# untitled.net
KiCad netlist of a schematic drawn in EAGLE
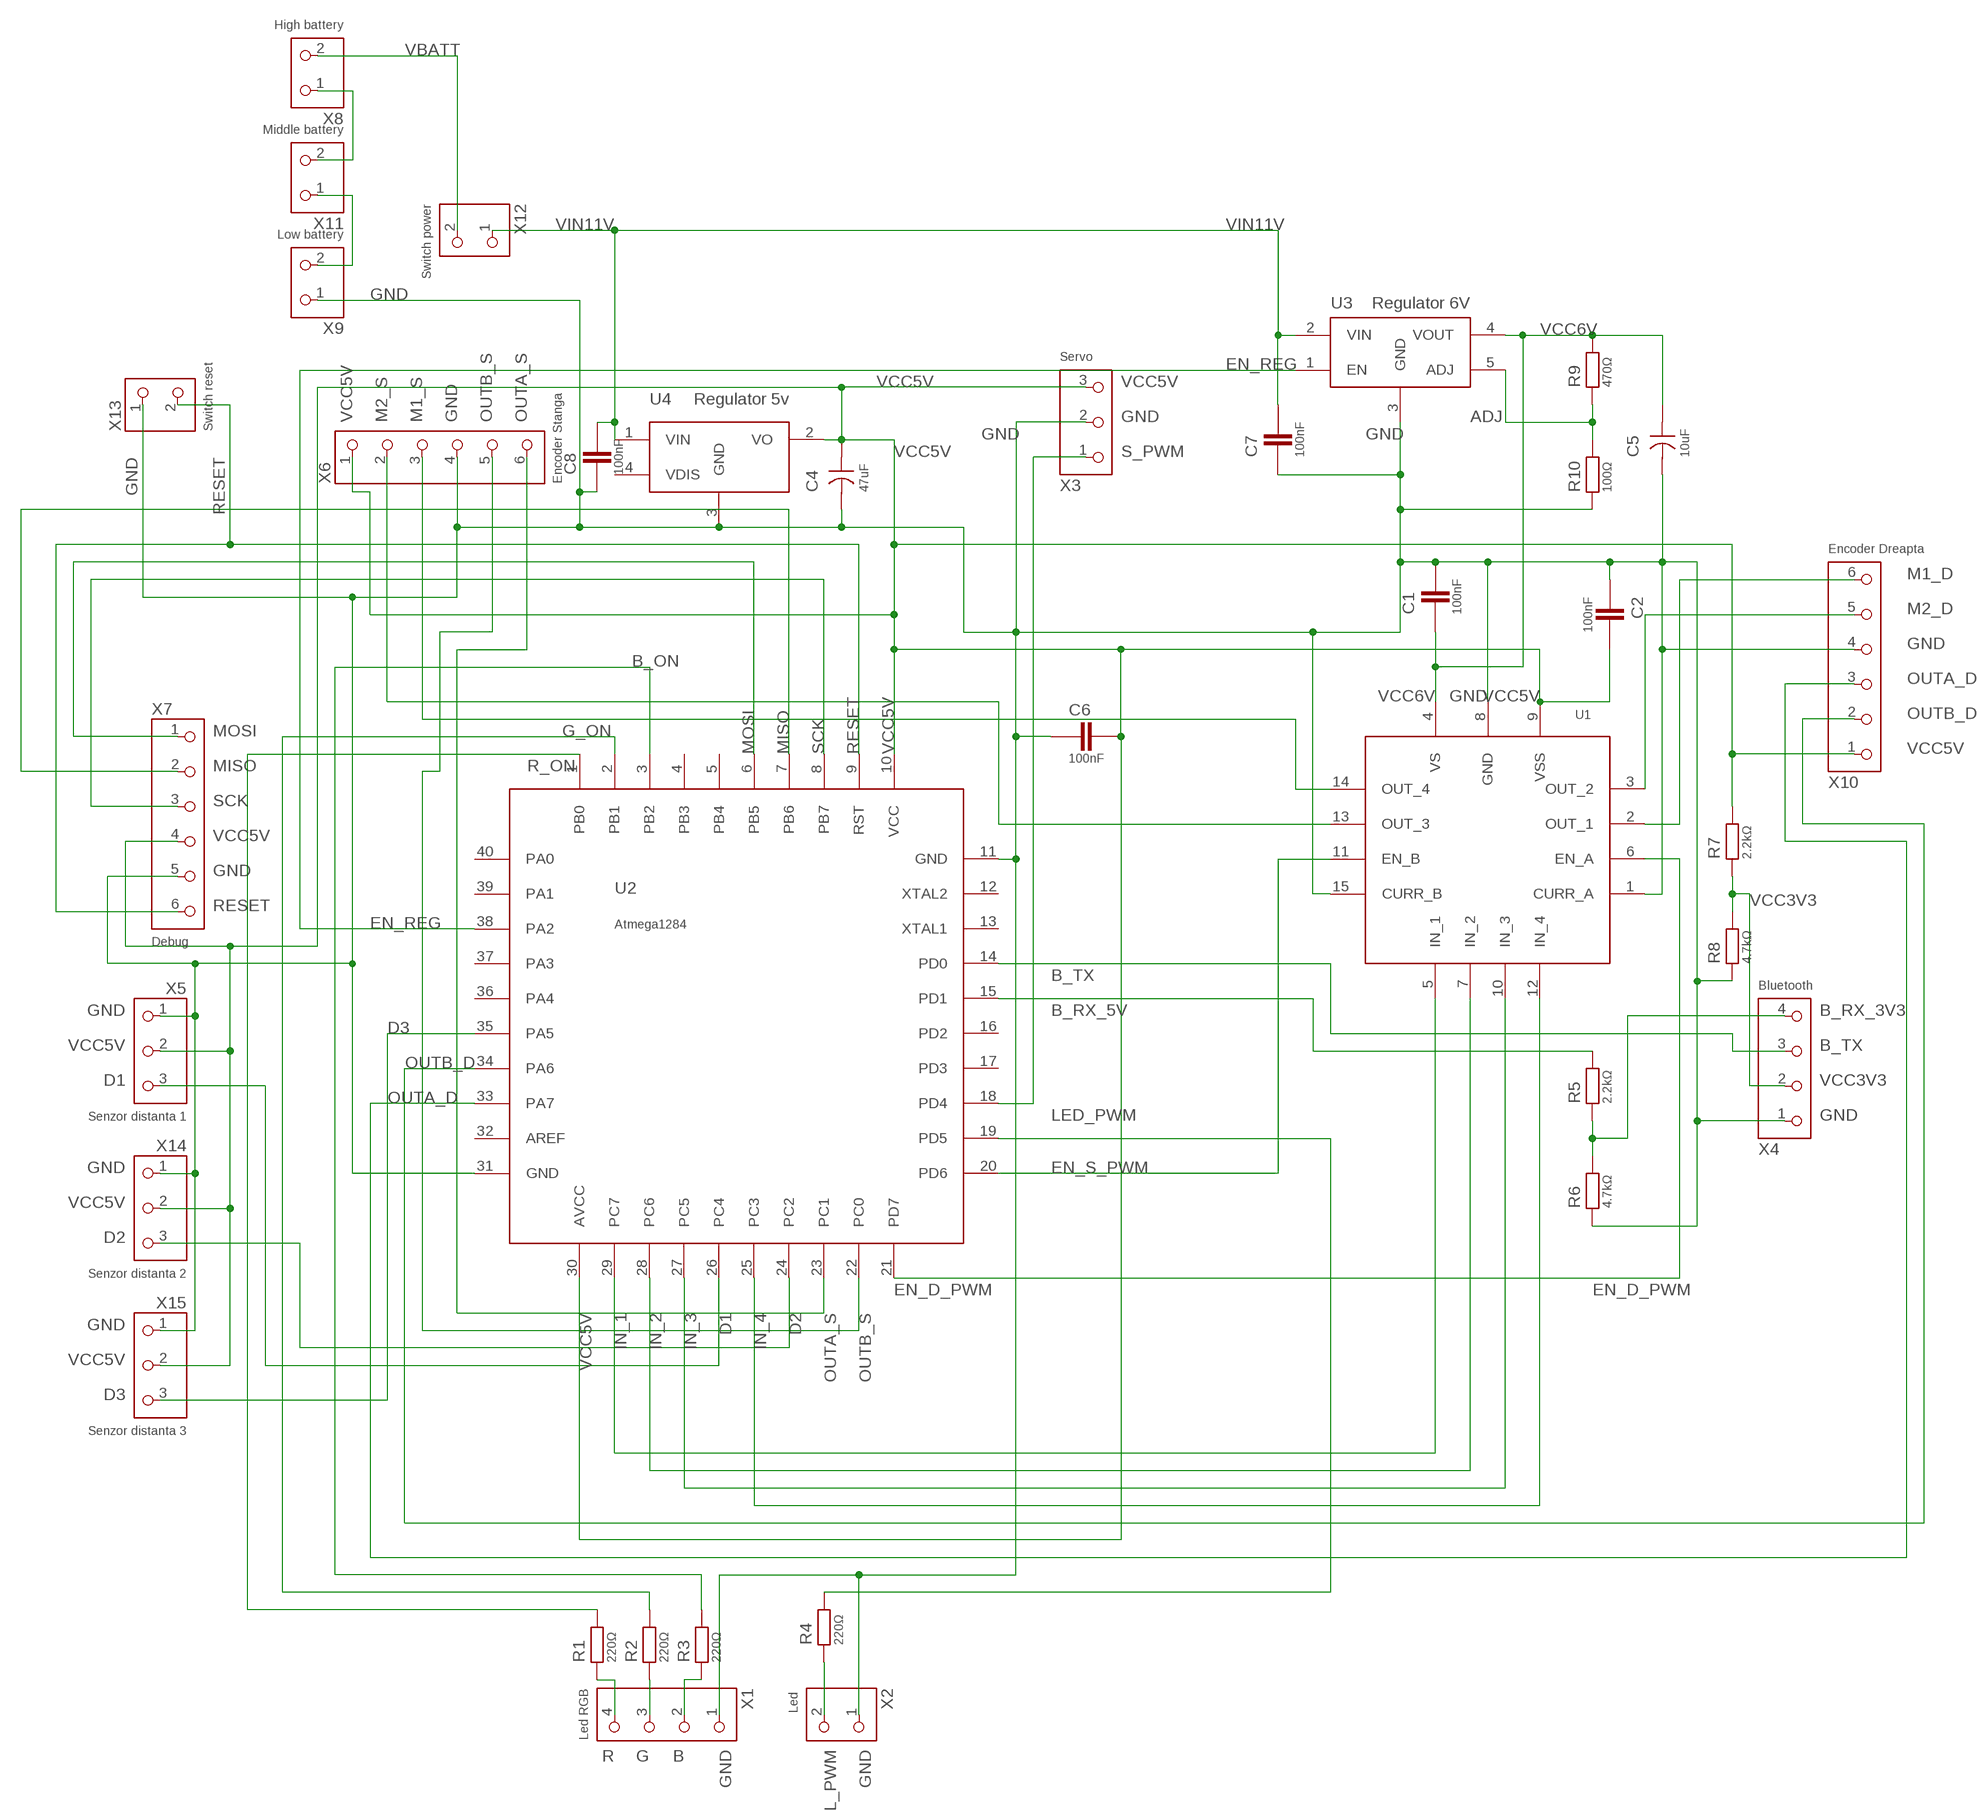
[diagram p0: schematic, sheet 1]

(export (version "E")
  (design (tool "Eeschema 10.0.6"))
  (components
    (comp (ref "C1")
      (value "100nF")
      (footprint "eagle-import:THT_2.54")
      (libsource (lib "eagle-import") (part "CAPACITORTHT_2.54"))
    )
    (comp (ref "C2")
      (value "100nF")
      (footprint "eagle-import:THT_2.54")
      (libsource (lib "eagle-import") (part "CAPACITORTHT_2.54"))
    )
    (comp (ref "C4")
      (value "47uF")
      (footprint "eagle-import:ELECTROLYTIC_5MM_PEFRBOARD")
      (libsource (lib "eagle-import") (part "ELECTROLYTIC_CAPACITOR5MM_PERFBOARD"))
    )
    (comp (ref "C5")
      (value "10uF")
      (footprint "eagle-import:ELECTROLYTIC_5MM_PEFRBOARD")
      (libsource (lib "eagle-import") (part "ELECTROLYTIC_CAPACITOR5MM_PERFBOARD"))
    )
    (comp (ref "C6")
      (value "100nF")
      (footprint "eagle-import:THT_2.54")
      (libsource (lib "eagle-import") (part "CAPACITORTHT_2.54"))
    )
    (comp (ref "C7")
      (value "100nF")
      (footprint "eagle-import:THT_2.54")
      (libsource (lib "eagle-import") (part "CAPACITORTHT_2.54"))
    )
    (comp (ref "C8")
      (value "100nF")
      (footprint "eagle-import:THT_2.54")
      (libsource (lib "eagle-import") (part "CAPACITORTHT_2.54"))
    )
    (comp (ref "R1")
      (value "220Ω")
      (footprint "eagle-import:THT_5.08")
      (libsource (lib "eagle-import") (part "RESISTORTHT_5.08"))
    )
    (comp (ref "R2")
      (value "220Ω")
      (footprint "eagle-import:THT_5.08")
      (libsource (lib "eagle-import") (part "RESISTORTHT_5.08"))
    )
    (comp (ref "R3")
      (value "220Ω")
      (footprint "eagle-import:THT_5.08")
      (libsource (lib "eagle-import") (part "RESISTORTHT_5.08"))
    )
    (comp (ref "R4")
      (value "220Ω")
      (footprint "eagle-import:THT_5.08")
      (libsource (lib "eagle-import") (part "RESISTORTHT_5.08"))
    )
    (comp (ref "R5")
      (value "2.2kΩ")
      (footprint "eagle-import:THT_2.54")
      (libsource (lib "eagle-import") (part "RESISTORTHT_2.54"))
    )
    (comp (ref "R6")
      (value "4.7kΩ")
      (footprint "eagle-import:THT_5.08")
      (libsource (lib "eagle-import") (part "RESISTORTHT_5.08"))
    )
    (comp (ref "R7")
      (value "2.2kΩ")
      (footprint "eagle-import:THT_5.08")
      (libsource (lib "eagle-import") (part "RESISTORTHT_5.08"))
    )
    (comp (ref "R8")
      (value "4.7kΩ")
      (footprint "eagle-import:THT_5.08")
      (libsource (lib "eagle-import") (part "RESISTORTHT_5.08"))
    )
    (comp (ref "R9")
      (value "470Ω")
      (footprint "eagle-import:THT_2.54")
      (libsource (lib "eagle-import") (part "RESISTORTHT_2.54"))
    )
    (comp (ref "R10")
      (value "100Ω")
      (footprint "eagle-import:THT_5.08")
      (libsource (lib "eagle-import") (part "RESISTORTHT_5.08"))
    )
    (comp (ref "U1")
      (value "L298NMULTIWATT15V_PERFBOARD")
      (footprint "eagle-import:MULTIWATT15V_PERFBOARD")
      (libsource (lib "eagle-import") (part "L298NMULTIWATT15V_PERFBOARD"))
    )
    (comp (ref "U2")
      (value "Atmega1284")
      (footprint "eagle-import:DIP-40")
      (libsource (lib "eagle-import") (part "ATMEGAPDIP"))
    )
    (comp (ref "U3")
      (value "Regulator 6V")
      (footprint "eagle-import:TO-220-5_PERFBOARD")
      (libsource (lib "eagle-import") (part "MIC29XXPERFBOARD"))
    )
    (comp (ref "U4")
      (value "Regulator 5v")
      (footprint "eagle-import:TO-220-4")
      (libsource (lib "eagle-import") (part "KA78R05C"))
    )
    (comp (ref "X1")
      (value "Led RGB")
      (footprint "eagle-import:MALE_PIN_1X4")
      (libsource (lib "eagle-import") (part "CONNECTOR_4PIN"))
    )
    (comp (ref "X2")
      (value "Led")
      (footprint "eagle-import:MALE_PIN_1X2")
      (libsource (lib "eagle-import") (part "CONNECTOR_2PINMALE_PIN"))
    )
    (comp (ref "X3")
      (value "Servo")
      (footprint "eagle-import:MALE_PIN_1X3")
      (libsource (lib "eagle-import") (part "CONNECTOR_3PIN"))
    )
    (comp (ref "X4")
      (value "Bluetooth")
      (footprint "eagle-import:MALE_PIN_1X4")
      (libsource (lib "eagle-import") (part "CONNECTOR_4PIN"))
    )
    (comp (ref "X5")
      (value "Senzor distanta 1")
      (footprint "eagle-import:MALE_PIN_1X3")
      (libsource (lib "eagle-import") (part "CONNECTOR_3PIN"))
    )
    (comp (ref "X6")
      (value "Encoder Stanga")
      (footprint "eagle-import:MALE_PIN_2X3")
      (libsource (lib "eagle-import") (part "CONNECTOR_6PIN2X3"))
    )
    (comp (ref "X7")
      (value "Debug")
      (footprint "eagle-import:MALE_PIN_2X3")
      (libsource (lib "eagle-import") (part "CONNECTOR_6PIN2X3"))
    )
    (comp (ref "X8")
      (value "High battery")
      (footprint "eagle-import:FEMALE_SCREW_1X2")
      (libsource (lib "eagle-import") (part "CONNECTOR_2PINFEMALE_SCREW"))
    )
    (comp (ref "X9")
      (value "Low battery")
      (footprint "eagle-import:FEMALE_SCREW_1X2")
      (libsource (lib "eagle-import") (part "CONNECTOR_2PINFEMALE_SCREW"))
    )
    (comp (ref "X10")
      (value "Encoder Dreapta")
      (footprint "eagle-import:MALE_PIN_2X3")
      (libsource (lib "eagle-import") (part "CONNECTOR_6PIN2X3"))
    )
    (comp (ref "X11")
      (value "Middle battery")
      (footprint "eagle-import:FEMALE_SCREW_1X2")
      (libsource (lib "eagle-import") (part "CONNECTOR_2PINFEMALE_SCREW"))
    )
    (comp (ref "X12")
      (value "Switch power")
      (footprint "eagle-import:MALE_PIN_1X2")
      (libsource (lib "eagle-import") (part "CONNECTOR_2PINMALE_PIN"))
    )
    (comp (ref "X13")
      (value "Switch reset")
      (footprint "eagle-import:MALE_PIN_1X2")
      (libsource (lib "eagle-import") (part "CONNECTOR_2PINMALE_PIN"))
    )
    (comp (ref "X14")
      (value "Senzor distanta 2")
      (footprint "eagle-import:MALE_PIN_1X3")
      (libsource (lib "eagle-import") (part "CONNECTOR_3PIN"))
    )
    (comp (ref "X15")
      (value "Senzor distanta 3")
      (footprint "eagle-import:MALE_PIN_1X3")
      (libsource (lib "eagle-import") (part "CONNECTOR_3PIN"))
    )
  )
  (nets
    (net (code "1") (name "/ADJ") (class "Default")
      (node (ref "R10") (pin "2") (pinfunction "P$2_2") (pintype "passive"))
      (node (ref "R9") (pin "1") (pinfunction "P$1_1") (pintype "passive"))
      (node (ref "U3") (pin "5") (pinfunction "ADJ_5") (pintype "input"))
    )
    (net (code "2") (name "/B") (class "Default")
      (node (ref "R3") (pin "1") (pinfunction "P$1_1") (pintype "passive"))
      (node (ref "X1") (pin "2") (pinfunction "2_2") (pintype "passive"))
    )
    (net (code "3") (name "/B_ON") (class "Default")
      (node (ref "R3") (pin "2") (pinfunction "P$2_2") (pintype "passive"))
      (node (ref "U2") (pin "3") (pinfunction "PB2_3") (pintype "bidirectional"))
    )
    (net (code "4") (name "/B_RX_3V3") (class "Default")
      (node (ref "R5") (pin "1") (pinfunction "P$1_1") (pintype "passive"))
      (node (ref "R6") (pin "2") (pinfunction "P$2_2") (pintype "passive"))
      (node (ref "X4") (pin "4") (pinfunction "4_4") (pintype "passive"))
    )
    (net (code "5") (name "/B_RX_5V") (class "Default")
      (node (ref "R5") (pin "2") (pinfunction "P$2_2") (pintype "passive"))
      (node (ref "U2") (pin "15") (pinfunction "PD1_15") (pintype "bidirectional"))
    )
    (net (code "6") (name "/B_TX") (class "Default")
      (node (ref "U2") (pin "14") (pinfunction "PD0_14") (pintype "bidirectional"))
      (node (ref "X4") (pin "3") (pinfunction "3_3") (pintype "passive"))
    )
    (net (code "7") (name "/D1") (class "Default")
      (node (ref "U2") (pin "26") (pinfunction "PC4_26") (pintype "bidirectional"))
      (node (ref "X5") (pin "3") (pinfunction "3_3") (pintype "passive"))
    )
    (net (code "8") (name "/D2") (class "Default")
      (node (ref "U2") (pin "24") (pinfunction "PC2_24") (pintype "bidirectional"))
      (node (ref "X14") (pin "3") (pinfunction "3_3") (pintype "passive"))
    )
    (net (code "9") (name "/D3") (class "Default")
      (node (ref "U2") (pin "35") (pinfunction "PA5_35") (pintype "bidirectional"))
      (node (ref "X15") (pin "3") (pinfunction "3_3") (pintype "passive"))
    )
    (net (code "10") (name "/EN_D_PWM") (class "Default")
      (node (ref "U1") (pin "6") (pinfunction "EN_A_6") (pintype "input"))
      (node (ref "U2") (pin "21") (pinfunction "PD7_21") (pintype "bidirectional"))
    )
    (net (code "11") (name "/EN_REG") (class "Default")
      (node (ref "U2") (pin "38") (pinfunction "PA2_38") (pintype "bidirectional"))
      (node (ref "U3") (pin "1") (pinfunction "EN_1") (pintype "input"))
    )
    (net (code "12") (name "/EN_S_PWM") (class "Default")
      (node (ref "U1") (pin "11") (pinfunction "EN_B_11") (pintype "input"))
      (node (ref "U2") (pin "20") (pinfunction "PD6_20") (pintype "bidirectional"))
    )
    (net (code "13") (name "/G") (class "Default")
      (node (ref "R2") (pin "1") (pinfunction "P$1_1") (pintype "passive"))
      (node (ref "X1") (pin "3") (pinfunction "3_3") (pintype "passive"))
    )
    (net (code "14") (name "/GND") (class "Default")
      (node (ref "C1") (pin "2") (pinfunction "P$2_2") (pintype "passive"))
      (node (ref "C2") (pin "1") (pinfunction "P$1_1") (pintype "passive"))
      (node (ref "C4") (pin "-") (pinfunction "-_-") (pintype "passive"))
      (node (ref "C5") (pin "-") (pinfunction "-_-") (pintype "passive"))
      (node (ref "C6") (pin "1") (pinfunction "P$1_1") (pintype "passive"))
      (node (ref "C7") (pin "1") (pinfunction "P$1_1") (pintype "passive"))
      (node (ref "C8") (pin "1") (pinfunction "P$1_1") (pintype "passive"))
      (node (ref "R10") (pin "1") (pinfunction "P$1_1") (pintype "passive"))
      (node (ref "R6") (pin "1") (pinfunction "P$1_1") (pintype "passive"))
      (node (ref "R8") (pin "1") (pinfunction "P$1_1") (pintype "passive"))
      (node (ref "U1") (pin "1") (pinfunction "CURR_A_1") (pintype "output"))
      (node (ref "U1") (pin "15") (pinfunction "CURR_B_15") (pintype "output"))
      (node (ref "U1") (pin "8") (pinfunction "GND_8") (pintype "power_in"))
      (node (ref "U2") (pin "11") (pinfunction "GND_11") (pintype "power_in"))
      (node (ref "U2") (pin "31") (pinfunction "GND_31") (pintype "power_in"))
      (node (ref "U3") (pin "3") (pinfunction "GND_3") (pintype "power_in"))
      (node (ref "U4") (pin "3") (pinfunction "GND_3") (pintype "power_in"))
      (node (ref "X1") (pin "1") (pinfunction "1_1") (pintype "passive"))
      (node (ref "X10") (pin "4") (pinfunction "4_4") (pintype "passive"))
      (node (ref "X13") (pin "1") (pinfunction "1_1") (pintype "passive"))
      (node (ref "X14") (pin "1") (pinfunction "1_1") (pintype "passive"))
      (node (ref "X15") (pin "1") (pinfunction "1_1") (pintype "passive"))
      (node (ref "X2") (pin "1") (pinfunction "1_1") (pintype "passive"))
      (node (ref "X3") (pin "2") (pinfunction "2_2") (pintype "passive"))
      (node (ref "X4") (pin "1") (pinfunction "1_1") (pintype "passive"))
      (node (ref "X5") (pin "1") (pinfunction "1_1") (pintype "passive"))
      (node (ref "X6") (pin "4") (pinfunction "4_4") (pintype "passive"))
      (node (ref "X7") (pin "5") (pinfunction "5_5") (pintype "passive"))
      (node (ref "X9") (pin "1") (pinfunction "1_1") (pintype "passive"))
    )
    (net (code "15") (name "/G_ON") (class "Default")
      (node (ref "R2") (pin "2") (pinfunction "P$2_2") (pintype "passive"))
      (node (ref "U2") (pin "2") (pinfunction "PB1_2") (pintype "bidirectional"))
    )
    (net (code "16") (name "/IN_1") (class "Default")
      (node (ref "U1") (pin "5") (pinfunction "IN_1_5") (pintype "input"))
      (node (ref "U2") (pin "29") (pinfunction "PC7_29") (pintype "bidirectional"))
    )
    (net (code "17") (name "/IN_2") (class "Default")
      (node (ref "U1") (pin "7") (pinfunction "IN_2_7") (pintype "input"))
      (node (ref "U2") (pin "28") (pinfunction "PC6_28") (pintype "bidirectional"))
    )
    (net (code "18") (name "/IN_3") (class "Default")
      (node (ref "U1") (pin "10") (pinfunction "IN_3_10") (pintype "input"))
      (node (ref "U2") (pin "27") (pinfunction "PC5_27") (pintype "bidirectional"))
    )
    (net (code "19") (name "/IN_4") (class "Default")
      (node (ref "U1") (pin "12") (pinfunction "IN_4_12") (pintype "input"))
      (node (ref "U2") (pin "25") (pinfunction "PC3_25") (pintype "bidirectional"))
    )
    (net (code "20") (name "/LED_PWM") (class "Default")
      (node (ref "R4") (pin "2") (pinfunction "P$2_2") (pintype "passive"))
      (node (ref "U2") (pin "19") (pinfunction "PD5_19") (pintype "bidirectional"))
    )
    (net (code "21") (name "/L_PWM") (class "Default")
      (node (ref "R4") (pin "1") (pinfunction "P$1_1") (pintype "passive"))
      (node (ref "X2") (pin "2") (pinfunction "2_2") (pintype "passive"))
    )
    (net (code "22") (name "/M1_D") (class "Default")
      (node (ref "U1") (pin "2") (pinfunction "OUT_1_2") (pintype "output"))
      (node (ref "X10") (pin "6") (pinfunction "6_6") (pintype "passive"))
    )
    (net (code "23") (name "/M1_S") (class "Default")
      (node (ref "U1") (pin "14") (pinfunction "OUT_4_14") (pintype "output"))
      (node (ref "X6") (pin "3") (pinfunction "3_3") (pintype "passive"))
    )
    (net (code "24") (name "/M2_D") (class "Default")
      (node (ref "U1") (pin "3") (pinfunction "OUT_2_3") (pintype "output"))
      (node (ref "X10") (pin "5") (pinfunction "5_5") (pintype "passive"))
    )
    (net (code "25") (name "/M2_S") (class "Default")
      (node (ref "U1") (pin "13") (pinfunction "OUT_3_13") (pintype "output"))
      (node (ref "X6") (pin "2") (pinfunction "2_2") (pintype "passive"))
    )
    (net (code "26") (name "/MISO") (class "Default")
      (node (ref "U2") (pin "7") (pinfunction "PB6_7") (pintype "bidirectional"))
      (node (ref "X7") (pin "2") (pinfunction "2_2") (pintype "passive"))
    )
    (net (code "27") (name "/MOSI") (class "Default")
      (node (ref "U2") (pin "6") (pinfunction "PB5_6") (pintype "bidirectional"))
      (node (ref "X7") (pin "1") (pinfunction "1_1") (pintype "passive"))
    )
    (net (code "28") (name "/OUTA_D") (class "Default")
      (node (ref "U2") (pin "33") (pinfunction "PA7_33") (pintype "bidirectional"))
      (node (ref "X10") (pin "3") (pinfunction "3_3") (pintype "passive"))
    )
    (net (code "29") (name "/OUTA_S") (class "Default")
      (node (ref "U2") (pin "23") (pinfunction "PC1_23") (pintype "bidirectional"))
      (node (ref "X6") (pin "6") (pinfunction "6_6") (pintype "passive"))
    )
    (net (code "30") (name "/OUTB_D") (class "Default")
      (node (ref "U2") (pin "34") (pinfunction "PA6_34") (pintype "bidirectional"))
      (node (ref "X10") (pin "2") (pinfunction "2_2") (pintype "passive"))
    )
    (net (code "31") (name "/OUTB_S") (class "Default")
      (node (ref "U2") (pin "22") (pinfunction "PC0_22") (pintype "bidirectional"))
      (node (ref "X6") (pin "5") (pinfunction "5_5") (pintype "passive"))
    )
    (net (code "32") (name "/R") (class "Default")
      (node (ref "R1") (pin "1") (pinfunction "P$1_1") (pintype "passive"))
      (node (ref "X1") (pin "4") (pinfunction "4_4") (pintype "passive"))
    )
    (net (code "33") (name "/RESET") (class "Default")
      (node (ref "U2") (pin "9") (pinfunction "RST_9") (pintype "input"))
      (node (ref "X13") (pin "2") (pinfunction "2_2") (pintype "passive"))
      (node (ref "X7") (pin "6") (pinfunction "6_6") (pintype "passive"))
    )
    (net (code "34") (name "/R_ON") (class "Default")
      (node (ref "R1") (pin "2") (pinfunction "P$2_2") (pintype "passive"))
      (node (ref "U2") (pin "1") (pinfunction "PB0_1") (pintype "bidirectional"))
    )
    (net (code "35") (name "/SCK") (class "Default")
      (node (ref "U2") (pin "8") (pinfunction "PB7_8") (pintype "bidirectional"))
      (node (ref "X7") (pin "3") (pinfunction "3_3") (pintype "passive"))
    )
    (net (code "36") (name "/S_PWM") (class "Default")
      (node (ref "U2") (pin "18") (pinfunction "PD4_18") (pintype "bidirectional"))
      (node (ref "X3") (pin "1") (pinfunction "1_1") (pintype "passive"))
    )
    (net (code "37") (name "/VBATT") (class "Default")
      (node (ref "X12") (pin "2") (pinfunction "2_2") (pintype "passive"))
      (node (ref "X8") (pin "2") (pinfunction "2_2") (pintype "passive"))
    )
    (net (code "38") (name "/VCC3V3") (class "Default")
      (node (ref "R7") (pin "1") (pinfunction "P$1_1") (pintype "passive"))
      (node (ref "R8") (pin "2") (pinfunction "P$2_2") (pintype "passive"))
      (node (ref "X4") (pin "2") (pinfunction "2_2") (pintype "passive"))
    )
    (net (code "39") (name "/VCC5V") (class "Default")
      (node (ref "C2") (pin "2") (pinfunction "P$2_2") (pintype "passive"))
      (node (ref "C4") (pin "+") (pinfunction "+_+") (pintype "passive"))
      (node (ref "C6") (pin "2") (pinfunction "P$2_2") (pintype "passive"))
      (node (ref "R7") (pin "2") (pinfunction "P$2_2") (pintype "passive"))
      (node (ref "U1") (pin "9") (pinfunction "VSS_9") (pintype "power_in"))
      (node (ref "U2") (pin "10") (pinfunction "VCC_10") (pintype "power_in"))
      (node (ref "U2") (pin "30") (pinfunction "AVCC_30") (pintype "power_in"))
      (node (ref "U4") (pin "2") (pinfunction "VO_2") (pintype "power_in"))
      (node (ref "X10") (pin "1") (pinfunction "1_1") (pintype "passive"))
      (node (ref "X14") (pin "2") (pinfunction "2_2") (pintype "passive"))
      (node (ref "X15") (pin "2") (pinfunction "2_2") (pintype "passive"))
      (node (ref "X3") (pin "3") (pinfunction "3_3") (pintype "passive"))
      (node (ref "X5") (pin "2") (pinfunction "2_2") (pintype "passive"))
      (node (ref "X6") (pin "1") (pinfunction "1_1") (pintype "passive"))
      (node (ref "X7") (pin "4") (pinfunction "4_4") (pintype "passive"))
    )
    (net (code "40") (name "/VCC6V") (class "Default")
      (node (ref "C1") (pin "1") (pinfunction "P$1_1") (pintype "passive"))
      (node (ref "C5") (pin "+") (pinfunction "+_+") (pintype "passive"))
      (node (ref "R9") (pin "2") (pinfunction "P$2_2") (pintype "passive"))
      (node (ref "U1") (pin "4") (pinfunction "VS_4") (pintype "power_in"))
      (node (ref "U3") (pin "4") (pinfunction "VOUT_4") (pintype "power_in"))
    )
    (net (code "41") (name "/VIN11V") (class "Default")
      (node (ref "C7") (pin "2") (pinfunction "P$2_2") (pintype "passive"))
      (node (ref "C8") (pin "2") (pinfunction "P$2_2") (pintype "passive"))
      (node (ref "U3") (pin "2") (pinfunction "VIN_2") (pintype "power_in"))
      (node (ref "U4") (pin "1") (pinfunction "VIN_1") (pintype "power_in"))
      (node (ref "X12") (pin "1") (pinfunction "1_1") (pintype "passive"))
    )
    (net (code "42") (name "Net-(X11-Pad1)") (class "Default")
      (node (ref "X11") (pin "1") (pinfunction "1_1") (pintype "passive"))
      (node (ref "X9") (pin "2") (pinfunction "2_2") (pintype "passive"))
    )
    (net (code "43") (name "Net-(X11-Pad2)") (class "Default")
      (node (ref "X11") (pin "2") (pinfunction "2_2") (pintype "passive"))
      (node (ref "X8") (pin "1") (pinfunction "1_1") (pintype "passive"))
    )
    (net (code "44") (name "unconnected-(U2-AREF-Pad32)") (class "Default")
      (node (ref "U2") (pin "32") (pinfunction "AREF_32") (pintype "bidirectional"))
    )
    (net (code "45") (name "unconnected-(U2-PA0-Pad40)") (class "Default")
      (node (ref "U2") (pin "40") (pinfunction "PA0_40") (pintype "bidirectional"))
    )
    (net (code "46") (name "unconnected-(U2-PA1-Pad39)") (class "Default")
      (node (ref "U2") (pin "39") (pinfunction "PA1_39") (pintype "bidirectional"))
    )
    (net (code "47") (name "unconnected-(U2-PA3-Pad37)") (class "Default")
      (node (ref "U2") (pin "37") (pinfunction "PA3_37") (pintype "bidirectional"))
    )
    (net (code "48") (name "unconnected-(U2-PA4-Pad36)") (class "Default")
      (node (ref "U2") (pin "36") (pinfunction "PA4_36") (pintype "bidirectional"))
    )
    (net (code "49") (name "unconnected-(U2-PB3-Pad4)") (class "Default")
      (node (ref "U2") (pin "4") (pinfunction "PB3_4") (pintype "bidirectional"))
    )
    (net (code "50") (name "unconnected-(U2-PB4-Pad5)") (class "Default")
      (node (ref "U2") (pin "5") (pinfunction "PB4_5") (pintype "bidirectional"))
    )
    (net (code "51") (name "unconnected-(U2-PD2-Pad16)") (class "Default")
      (node (ref "U2") (pin "16") (pinfunction "PD2_16") (pintype "bidirectional"))
    )
    (net (code "52") (name "unconnected-(U2-PD3-Pad17)") (class "Default")
      (node (ref "U2") (pin "17") (pinfunction "PD3_17") (pintype "bidirectional"))
    )
    (net (code "53") (name "unconnected-(U2-XTAL1-Pad13)") (class "Default")
      (node (ref "U2") (pin "13") (pinfunction "XTAL1_13") (pintype "input"))
    )
    (net (code "54") (name "unconnected-(U2-XTAL2-Pad12)") (class "Default")
      (node (ref "U2") (pin "12") (pinfunction "XTAL2_12") (pintype "input"))
    )
    (net (code "55") (name "unconnected-(U4-VDIS-Pad4)") (class "Default")
      (node (ref "U4") (pin "4") (pinfunction "VDIS_4") (pintype "input"))
    )
  )
)
